# MCU-io.net
KiCad netlist of a schematic drawn in Altium Designer
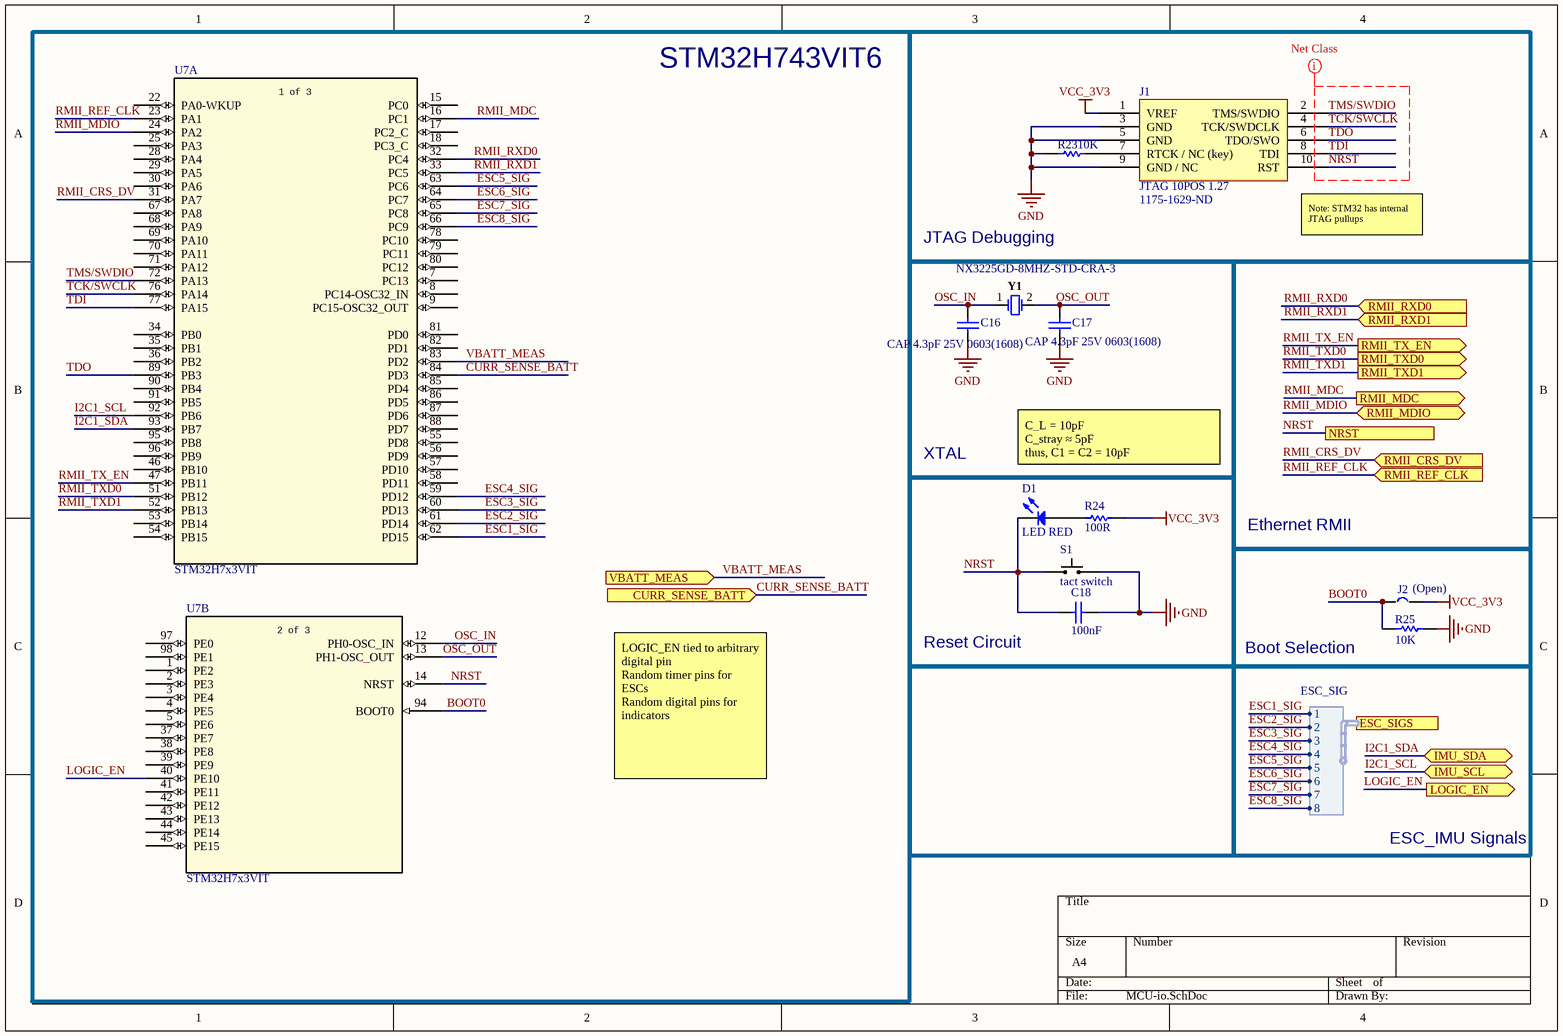
[diagram p0: MCU-io.SchDoc]

(export (version "E")
  (design (tool "Eeschema 10.0.6"))
  (components
    (comp (ref "C16")
      (value "CAP 4.3pF 25V 0603(1608)")
      (footprint "CAPC0603(1608)100_L")
      (description "CAP 4.3pF 25V ±0.5pF 0603 (1608 Metric) Thickness 1mm SMD")
      (fields (field (name "TOLERANCE") "Â±0.5pF"))
      (libsource (lib "Altium Content Vault") (part "CAP"))
    )
    (comp (ref "C17")
      (value "CAP 4.3pF 25V 0603(1608)")
      (footprint "CAPC0603(1608)100_L")
      (description "CAP 4.3pF 25V ±0.5pF 0603 (1608 Metric) Thickness 1mm SMD")
      (fields (field (name "TOLERANCE") "Â±0.5pF"))
      (libsource (lib "Altium Content Vault") (part "CAP"))
    )
    (comp (ref "C18")
      (value "100nF")
      (footprint "CAPC0603(1608)100_N")
      (description "CAP 100nF 10V ±10% 0603 (1608 Metric) Thickness 1mm SMD")
      (fields (field (name "TOLERANCE") "Â±10%"))
      (libsource (lib "Altium Content Vault") (part "CAP"))
    )
    (comp (ref "D1")
      (value "LED RED")
      (footprint "LED_0805")
      (description "led")
      (fields
        (field (name "MANUFACTURER") "Lite-On Inc.")
        (field (name "MANUFACTURER PART NUMBER") "LTST-C171KRKT")
      )
      (libsource (lib "CMR_Miscellaneous_Devices") (part "LED0"))
    )
    (comp (ref "J1")
      (value "JTAG 10POS 1.27")
      (footprint "5x2 JTAG SMD")
      (fields (field (name "SUPPLIER PART NUMBER 1") "1175-1629-ND"))
      (libsource (lib "CMR_Miscellaneous_Devices") (part "jtag 10pos mini"))
    )
    (comp (ref "J2")
      (value "(Open)")
      (footprint "Solder Jumper")
      (description "Jumper")
      (libsource (lib "CMR_PCB_Components") (part "Jumper"))
    )
    (comp (ref "R23")
      (value "10K")
      (footprint "RESC0603(1608)_N")
      (description "10K 0.1W 5% 0603 (1608 Metric)  SMD")
      (fields (field (name "TOLERANCE") "5 %") (field (name "POWER") "0.1 W"))
      (libsource (lib "Altium Content Vault") (part "RES"))
    )
    (comp (ref "R24")
      (value "100R")
      (footprint "RESC0603(1608)_L")
      (description "100R 0.1W 5% 0603 (1608 Metric)  SMD")
      (fields (field (name "TOLERANCE") "5 %") (field (name "POWER") "0.1 W"))
      (libsource (lib "Altium Content Vault") (part "RES"))
    )
    (comp (ref "R25")
      (value "10K")
      (footprint "RESC0603(1608)_N")
      (description "10K 0.1W 5% 0603 (1608 Metric)  SMD")
      (fields (field (name "TOLERANCE") "5 %") (field (name "POWER") "0.1 W"))
      (libsource (lib "Altium Content Vault") (part "RES"))
    )
    (comp (ref "S1")
      (value "tact switch")
      (footprint "EVP-AA202K")
      (description "EVP-AA Momentary Switch SPST-NO")
      (fields (field (name "PART NUMBER") "EVP-AA202K"))
      (libsource (lib "CMR_Miscellaneous_Devices") (part "EVP-AA Switch"))
    )
    (comp (ref "U7")
      (value "STM32H7x3VIT")
      (footprint "LQFP100-14x14mm")
      (description "Imported")
      (fields
        (field (name "MANUFACTURER_PART_NUMBER") "stm32h7x3vit")
        (field (name "COPYRIGHT") "Copyright (C) 2016 Accelerated Designs. All rights reserved")
      )
      (libsource (lib "TAUV_Components") (part "STM32H7x3VIT"))
    )
    (comp (ref "Y1")
      (value "NX3225GD-8MHZ-STD-CRA-3")
      (footprint "NDK-NX3225GD-8MHZ-STD-CRA-3_V")
      (description "Crystal Unit, 8 MHz, 8 pF, -40 to 150 degC, 2-Pin SMD, RoHS, Tape and Reel")
      (fields (field (name "MANUFACTURER") "NDK"))
      (libsource (lib "Altium Content Vault") (part "XTAL-1-2-2"))
    )
  )
  (nets
    (net (code "2") (name "/BOOT0") (class "Default")
      (node (ref "J2") (pin "1") (pinfunction "1_1") (pintype "passive"))
      (node (ref "R25") (pin "1") (pinfunction "1_1") (pintype "passive"))
      (node (ref "U7") (pin "94") (pinfunction "BOOT0_94") (pintype "input"))
    )
    (net (code "3") (name "/CURR_SENSE_BATT") (class "Default")
      (node (ref "U7") (pin "84") (pinfunction "PD3_84") (pintype "bidirectional"))
    )
    (net (code "4") (name "/ESC1_SIG") (class "Default")
      (node (ref "U7") (pin "62") (pinfunction "PD15_62") (pintype "bidirectional"))
    )
    (net (code "5") (name "/ESC2_SIG") (class "Default")
      (node (ref "U7") (pin "61") (pinfunction "PD14_61") (pintype "bidirectional"))
    )
    (net (code "6") (name "/ESC3_SIG") (class "Default")
      (node (ref "U7") (pin "60") (pinfunction "PD13_60") (pintype "bidirectional"))
    )
    (net (code "7") (name "/ESC4_SIG") (class "Default")
      (node (ref "U7") (pin "59") (pinfunction "PD12_59") (pintype "bidirectional"))
    )
    (net (code "8") (name "/ESC5_SIG") (class "Default")
      (node (ref "U7") (pin "63") (pinfunction "PC6_63") (pintype "bidirectional"))
    )
    (net (code "9") (name "/ESC6_SIG") (class "Default")
      (node (ref "U7") (pin "64") (pinfunction "PC7_64") (pintype "bidirectional"))
    )
    (net (code "10") (name "/ESC7_SIG") (class "Default")
      (node (ref "U7") (pin "65") (pinfunction "PC8_65") (pintype "bidirectional"))
    )
    (net (code "11") (name "/ESC8_SIG") (class "Default")
      (node (ref "U7") (pin "66") (pinfunction "PC9_66") (pintype "bidirectional"))
    )
    (net (code "12") (name "/I2C1_SCL") (class "Default")
      (node (ref "U7") (pin "92") (pinfunction "PB6_92") (pintype "bidirectional"))
    )
    (net (code "13") (name "/I2C1_SDA") (class "Default")
      (node (ref "U7") (pin "93") (pinfunction "PB7_93") (pintype "bidirectional"))
    )
    (net (code "14") (name "/LOGIC_EN") (class "Default")
      (node (ref "U7") (pin "40") (pinfunction "PE10_40") (pintype "bidirectional"))
    )
    (net (code "15") (name "/NRST") (class "Default")
      (node (ref "C18") (pin "2") (pinfunction "2_2") (pintype "passive"))
      (node (ref "D1") (pin "1") (pinfunction "K_1") (pintype "passive"))
      (node (ref "J1") (pin "10") (pinfunction "RST_10") (pintype "passive"))
      (node (ref "S1") (pin "1") (pinfunction "1_1") (pintype "passive"))
      (node (ref "U7") (pin "14") (pinfunction "NRST_14") (pintype "bidirectional"))
    )
    (net (code "16") (name "/OSC_IN") (class "Default")
      (node (ref "C16") (pin "2") (pinfunction "2_2") (pintype "passive"))
      (node (ref "U7") (pin "12") (pinfunction "PH0-OSC_IN_12") (pintype "bidirectional"))
      (node (ref "Y1") (pin "1") (pinfunction "1_1") (pintype "passive"))
    )
    (net (code "17") (name "/OSC_OUT") (class "Default")
      (node (ref "C17") (pin "2") (pinfunction "2_2") (pintype "passive"))
      (node (ref "U7") (pin "13") (pinfunction "PH1-OSC_OUT_13") (pintype "bidirectional"))
      (node (ref "Y1") (pin "2") (pinfunction "2_2") (pintype "passive"))
    )
    (net (code "18") (name "/RMII_CRS_DV") (class "Default")
      (node (ref "U7") (pin "31") (pinfunction "PA7_31") (pintype "bidirectional"))
    )
    (net (code "19") (name "/RMII_MDC") (class "Default")
      (node (ref "U7") (pin "16") (pinfunction "PC1_16") (pintype "bidirectional"))
    )
    (net (code "20") (name "/RMII_MDIO") (class "Default")
      (node (ref "U7") (pin "24") (pinfunction "PA2_24") (pintype "bidirectional"))
    )
    (net (code "21") (name "/RMII_REF_CLK") (class "Default")
      (node (ref "U7") (pin "23") (pinfunction "PA1_23") (pintype "bidirectional"))
    )
    (net (code "22") (name "/RMII_RXD0") (class "Default")
      (node (ref "U7") (pin "32") (pinfunction "PC4_32") (pintype "bidirectional"))
    )
    (net (code "23") (name "/RMII_RXD1") (class "Default")
      (node (ref "U7") (pin "33") (pinfunction "PC5_33") (pintype "bidirectional"))
    )
    (net (code "24") (name "/RMII_TXD0") (class "Default")
      (node (ref "U7") (pin "51") (pinfunction "PB12_51") (pintype "bidirectional"))
    )
    (net (code "25") (name "/RMII_TXD1") (class "Default")
      (node (ref "U7") (pin "52") (pinfunction "PB13_52") (pintype "bidirectional"))
    )
    (net (code "26") (name "/RMII_TX_EN") (class "Default")
      (node (ref "U7") (pin "47") (pinfunction "PB11_47") (pintype "bidirectional"))
    )
    (net (code "27") (name "/TCK{slash}SWCLK") (class "Default")
      (node (ref "J1") (pin "4") (pinfunction "TCK/SWDCLK_4") (pintype "passive"))
      (node (ref "U7") (pin "76") (pinfunction "PA14_76") (pintype "bidirectional"))
    )
    (net (code "28") (name "/TDI") (class "Default")
      (node (ref "J1") (pin "8") (pinfunction "TDI_8") (pintype "passive"))
      (node (ref "U7") (pin "77") (pinfunction "PA15_77") (pintype "bidirectional"))
    )
    (net (code "29") (name "/TDO") (class "Default")
      (node (ref "J1") (pin "6") (pinfunction "TDO/SWO_6") (pintype "passive"))
      (node (ref "U7") (pin "89") (pinfunction "PB3_89") (pintype "bidirectional"))
    )
    (net (code "30") (name "/TMS{slash}SWDIO") (class "Default")
      (node (ref "J1") (pin "2") (pinfunction "TMS/SWDIO_2") (pintype "passive"))
      (node (ref "U7") (pin "72") (pinfunction "PA13_72") (pintype "bidirectional"))
    )
    (net (code "31") (name "/VBATT_MEAS") (class "Default")
      (node (ref "U7") (pin "83") (pinfunction "PD2_83") (pintype "bidirectional"))
    )
    (net (code "33") (name "GND") (class "Default")
      (node (ref "C16") (pin "1") (pinfunction "1_1") (pintype "passive"))
      (node (ref "C17") (pin "1") (pinfunction "1_1") (pintype "passive"))
      (node (ref "C18") (pin "1") (pinfunction "1_1") (pintype "passive"))
      (node (ref "J1") (pin "3") (pinfunction "GND_3") (pintype "passive"))
      (node (ref "J1") (pin "5") (pinfunction "GND_5") (pintype "passive"))
      (node (ref "J1") (pin "9") (pinfunction "GND_/_NC_9") (pintype "passive"))
      (node (ref "R23") (pin "1") (pinfunction "1_1") (pintype "passive"))
      (node (ref "R25") (pin "2") (pinfunction "2_2") (pintype "passive"))
      (node (ref "S1") (pin "2") (pinfunction "2_2") (pintype "passive"))
    )
    (net (code "34") (name "Net-(D1-A)") (class "Default")
      (node (ref "D1") (pin "2") (pinfunction "A_2") (pintype "passive"))
      (node (ref "R24") (pin "1") (pinfunction "1_1") (pintype "passive"))
    )
    (net (code "35") (name "Net-(J1-RTCK_{slash}_NC_(key))") (class "Default")
      (node (ref "J1") (pin "7") (pinfunction "RTCK_/_NC_(key)_7") (pintype "passive"))
      (node (ref "R23") (pin "2") (pinfunction "2_2") (pintype "passive"))
    )
    (net (code "36") (name "VCC_3V3") (class "Default")
      (node (ref "J1") (pin "1") (pinfunction "VREF_1") (pintype "passive"))
      (node (ref "J2") (pin "2") (pinfunction "2_2") (pintype "passive"))
      (node (ref "R24") (pin "2") (pinfunction "2_2") (pintype "passive"))
    )
    (net (code "37") (name "unconnected-(U7A-PA0-WKUP-Pad22)") (class "Default")
      (node (ref "U7") (pin "22") (pinfunction "PA0-WKUP_22") (pintype "bidirectional"))
    )
    (net (code "38") (name "unconnected-(U7A-PA3-Pad25)") (class "Default")
      (node (ref "U7") (pin "25") (pinfunction "PA3_25") (pintype "bidirectional"))
    )
    (net (code "39") (name "unconnected-(U7A-PA4-Pad28)") (class "Default")
      (node (ref "U7") (pin "28") (pinfunction "PA4_28") (pintype "bidirectional"))
    )
    (net (code "40") (name "unconnected-(U7A-PA5-Pad29)") (class "Default")
      (node (ref "U7") (pin "29") (pinfunction "PA5_29") (pintype "bidirectional"))
    )
    (net (code "41") (name "unconnected-(U7A-PA6-Pad30)") (class "Default")
      (node (ref "U7") (pin "30") (pinfunction "PA6_30") (pintype "bidirectional"))
    )
    (net (code "42") (name "unconnected-(U7A-PA8-Pad67)") (class "Default")
      (node (ref "U7") (pin "67") (pinfunction "PA8_67") (pintype "bidirectional"))
    )
    (net (code "43") (name "unconnected-(U7A-PA9-Pad68)") (class "Default")
      (node (ref "U7") (pin "68") (pinfunction "PA9_68") (pintype "bidirectional"))
    )
    (net (code "44") (name "unconnected-(U7A-PA10-Pad69)") (class "Default")
      (node (ref "U7") (pin "69") (pinfunction "PA10_69") (pintype "bidirectional"))
    )
    (net (code "45") (name "unconnected-(U7A-PA11-Pad70)") (class "Default")
      (node (ref "U7") (pin "70") (pinfunction "PA11_70") (pintype "bidirectional"))
    )
    (net (code "46") (name "unconnected-(U7A-PA12-Pad71)") (class "Default")
      (node (ref "U7") (pin "71") (pinfunction "PA12_71") (pintype "bidirectional"))
    )
    (net (code "47") (name "unconnected-(U7A-PB0-Pad34)") (class "Default")
      (node (ref "U7") (pin "34") (pinfunction "PB0_34") (pintype "bidirectional"))
    )
    (net (code "48") (name "unconnected-(U7A-PB1-Pad35)") (class "Default")
      (node (ref "U7") (pin "35") (pinfunction "PB1_35") (pintype "bidirectional"))
    )
    (net (code "49") (name "unconnected-(U7A-PB2-Pad36)") (class "Default")
      (node (ref "U7") (pin "36") (pinfunction "PB2_36") (pintype "bidirectional"))
    )
    (net (code "50") (name "unconnected-(U7A-PB4-Pad90)") (class "Default")
      (node (ref "U7") (pin "90") (pinfunction "PB4_90") (pintype "bidirectional"))
    )
    (net (code "51") (name "unconnected-(U7A-PB5-Pad91)") (class "Default")
      (node (ref "U7") (pin "91") (pinfunction "PB5_91") (pintype "bidirectional"))
    )
    (net (code "52") (name "unconnected-(U7A-PB8-Pad95)") (class "Default")
      (node (ref "U7") (pin "95") (pinfunction "PB8_95") (pintype "bidirectional"))
    )
    (net (code "53") (name "unconnected-(U7A-PB9-Pad96)") (class "Default")
      (node (ref "U7") (pin "96") (pinfunction "PB9_96") (pintype "bidirectional"))
    )
    (net (code "54") (name "unconnected-(U7A-PB10-Pad46)") (class "Default")
      (node (ref "U7") (pin "46") (pinfunction "PB10_46") (pintype "bidirectional"))
    )
    (net (code "55") (name "unconnected-(U7A-PB14-Pad53)") (class "Default")
      (node (ref "U7") (pin "53") (pinfunction "PB14_53") (pintype "bidirectional"))
    )
    (net (code "56") (name "unconnected-(U7A-PB15-Pad54)") (class "Default")
      (node (ref "U7") (pin "54") (pinfunction "PB15_54") (pintype "bidirectional"))
    )
    (net (code "57") (name "unconnected-(U7A-PC0-Pad15)") (class "Default")
      (node (ref "U7") (pin "15") (pinfunction "PC0_15") (pintype "bidirectional"))
    )
    (net (code "58") (name "unconnected-(U7A-PC2_C-Pad17)") (class "Default")
      (node (ref "U7") (pin "17") (pinfunction "PC2_C_17") (pintype "bidirectional"))
    )
    (net (code "59") (name "unconnected-(U7A-PC3_C-Pad18)") (class "Default")
      (node (ref "U7") (pin "18") (pinfunction "PC3_C_18") (pintype "bidirectional"))
    )
    (net (code "60") (name "unconnected-(U7A-PC10-Pad78)") (class "Default")
      (node (ref "U7") (pin "78") (pinfunction "PC10_78") (pintype "bidirectional"))
    )
    (net (code "61") (name "unconnected-(U7A-PC11-Pad79)") (class "Default")
      (node (ref "U7") (pin "79") (pinfunction "PC11_79") (pintype "bidirectional"))
    )
    (net (code "62") (name "unconnected-(U7A-PC12-Pad80)") (class "Default")
      (node (ref "U7") (pin "80") (pinfunction "PC12_80") (pintype "bidirectional"))
    )
    (net (code "63") (name "unconnected-(U7A-PC13-Pad7)") (class "Default")
      (node (ref "U7") (pin "7") (pinfunction "PC13_7") (pintype "bidirectional"))
    )
    (net (code "64") (name "unconnected-(U7A-PC14-OSC32_IN-Pad8)") (class "Default")
      (node (ref "U7") (pin "8") (pinfunction "PC14-OSC32_IN_8") (pintype "bidirectional"))
    )
    (net (code "65") (name "unconnected-(U7A-PC15-OSC32_OUT-Pad9)") (class "Default")
      (node (ref "U7") (pin "9") (pinfunction "PC15-OSC32_OUT_9") (pintype "bidirectional"))
    )
    (net (code "66") (name "unconnected-(U7A-PD0-Pad81)") (class "Default")
      (node (ref "U7") (pin "81") (pinfunction "PD0_81") (pintype "bidirectional"))
    )
    (net (code "67") (name "unconnected-(U7A-PD1-Pad82)") (class "Default")
      (node (ref "U7") (pin "82") (pinfunction "PD1_82") (pintype "bidirectional"))
    )
    (net (code "68") (name "unconnected-(U7A-PD4-Pad85)") (class "Default")
      (node (ref "U7") (pin "85") (pinfunction "PD4_85") (pintype "bidirectional"))
    )
    (net (code "69") (name "unconnected-(U7A-PD5-Pad86)") (class "Default")
      (node (ref "U7") (pin "86") (pinfunction "PD5_86") (pintype "bidirectional"))
    )
    (net (code "70") (name "unconnected-(U7A-PD6-Pad87)") (class "Default")
      (node (ref "U7") (pin "87") (pinfunction "PD6_87") (pintype "bidirectional"))
    )
    (net (code "71") (name "unconnected-(U7A-PD7-Pad88)") (class "Default")
      (node (ref "U7") (pin "88") (pinfunction "PD7_88") (pintype "bidirectional"))
    )
    (net (code "72") (name "unconnected-(U7A-PD8-Pad55)") (class "Default")
      (node (ref "U7") (pin "55") (pinfunction "PD8_55") (pintype "bidirectional"))
    )
    (net (code "73") (name "unconnected-(U7A-PD9-Pad56)") (class "Default")
      (node (ref "U7") (pin "56") (pinfunction "PD9_56") (pintype "bidirectional"))
    )
    (net (code "74") (name "unconnected-(U7A-PD10-Pad57)") (class "Default")
      (node (ref "U7") (pin "57") (pinfunction "PD10_57") (pintype "bidirectional"))
    )
    (net (code "75") (name "unconnected-(U7A-PD11-Pad58)") (class "Default")
      (node (ref "U7") (pin "58") (pinfunction "PD11_58") (pintype "bidirectional"))
    )
    (net (code "76") (name "unconnected-(U7B-PE0-Pad97)") (class "Default")
      (node (ref "U7") (pin "97") (pinfunction "PE0_97") (pintype "bidirectional"))
    )
    (net (code "77") (name "unconnected-(U7B-PE1-Pad98)") (class "Default")
      (node (ref "U7") (pin "98") (pinfunction "PE1_98") (pintype "bidirectional"))
    )
    (net (code "78") (name "unconnected-(U7B-PE2-Pad1)") (class "Default")
      (node (ref "U7") (pin "1") (pinfunction "PE2_1") (pintype "bidirectional"))
    )
    (net (code "79") (name "unconnected-(U7B-PE3-Pad2)") (class "Default")
      (node (ref "U7") (pin "2") (pinfunction "PE3_2") (pintype "bidirectional"))
    )
    (net (code "80") (name "unconnected-(U7B-PE4-Pad3)") (class "Default")
      (node (ref "U7") (pin "3") (pinfunction "PE4_3") (pintype "bidirectional"))
    )
    (net (code "81") (name "unconnected-(U7B-PE5-Pad4)") (class "Default")
      (node (ref "U7") (pin "4") (pinfunction "PE5_4") (pintype "bidirectional"))
    )
    (net (code "82") (name "unconnected-(U7B-PE6-Pad5)") (class "Default")
      (node (ref "U7") (pin "5") (pinfunction "PE6_5") (pintype "bidirectional"))
    )
    (net (code "83") (name "unconnected-(U7B-PE7-Pad37)") (class "Default")
      (node (ref "U7") (pin "37") (pinfunction "PE7_37") (pintype "bidirectional"))
    )
    (net (code "84") (name "unconnected-(U7B-PE8-Pad38)") (class "Default")
      (node (ref "U7") (pin "38") (pinfunction "PE8_38") (pintype "bidirectional"))
    )
    (net (code "85") (name "unconnected-(U7B-PE9-Pad39)") (class "Default")
      (node (ref "U7") (pin "39") (pinfunction "PE9_39") (pintype "bidirectional"))
    )
    (net (code "86") (name "unconnected-(U7B-PE11-Pad41)") (class "Default")
      (node (ref "U7") (pin "41") (pinfunction "PE11_41") (pintype "bidirectional"))
    )
    (net (code "87") (name "unconnected-(U7B-PE12-Pad42)") (class "Default")
      (node (ref "U7") (pin "42") (pinfunction "PE12_42") (pintype "bidirectional"))
    )
    (net (code "88") (name "unconnected-(U7B-PE13-Pad43)") (class "Default")
      (node (ref "U7") (pin "43") (pinfunction "PE13_43") (pintype "bidirectional"))
    )
    (net (code "89") (name "unconnected-(U7B-PE14-Pad44)") (class "Default")
      (node (ref "U7") (pin "44") (pinfunction "PE14_44") (pintype "bidirectional"))
    )
    (net (code "90") (name "unconnected-(U7B-PE15-Pad45)") (class "Default")
      (node (ref "U7") (pin "45") (pinfunction "PE15_45") (pintype "bidirectional"))
    )
  )
)
